# SCH_GW.net
KiCad netlist of a schematic drawn in Altium Designer
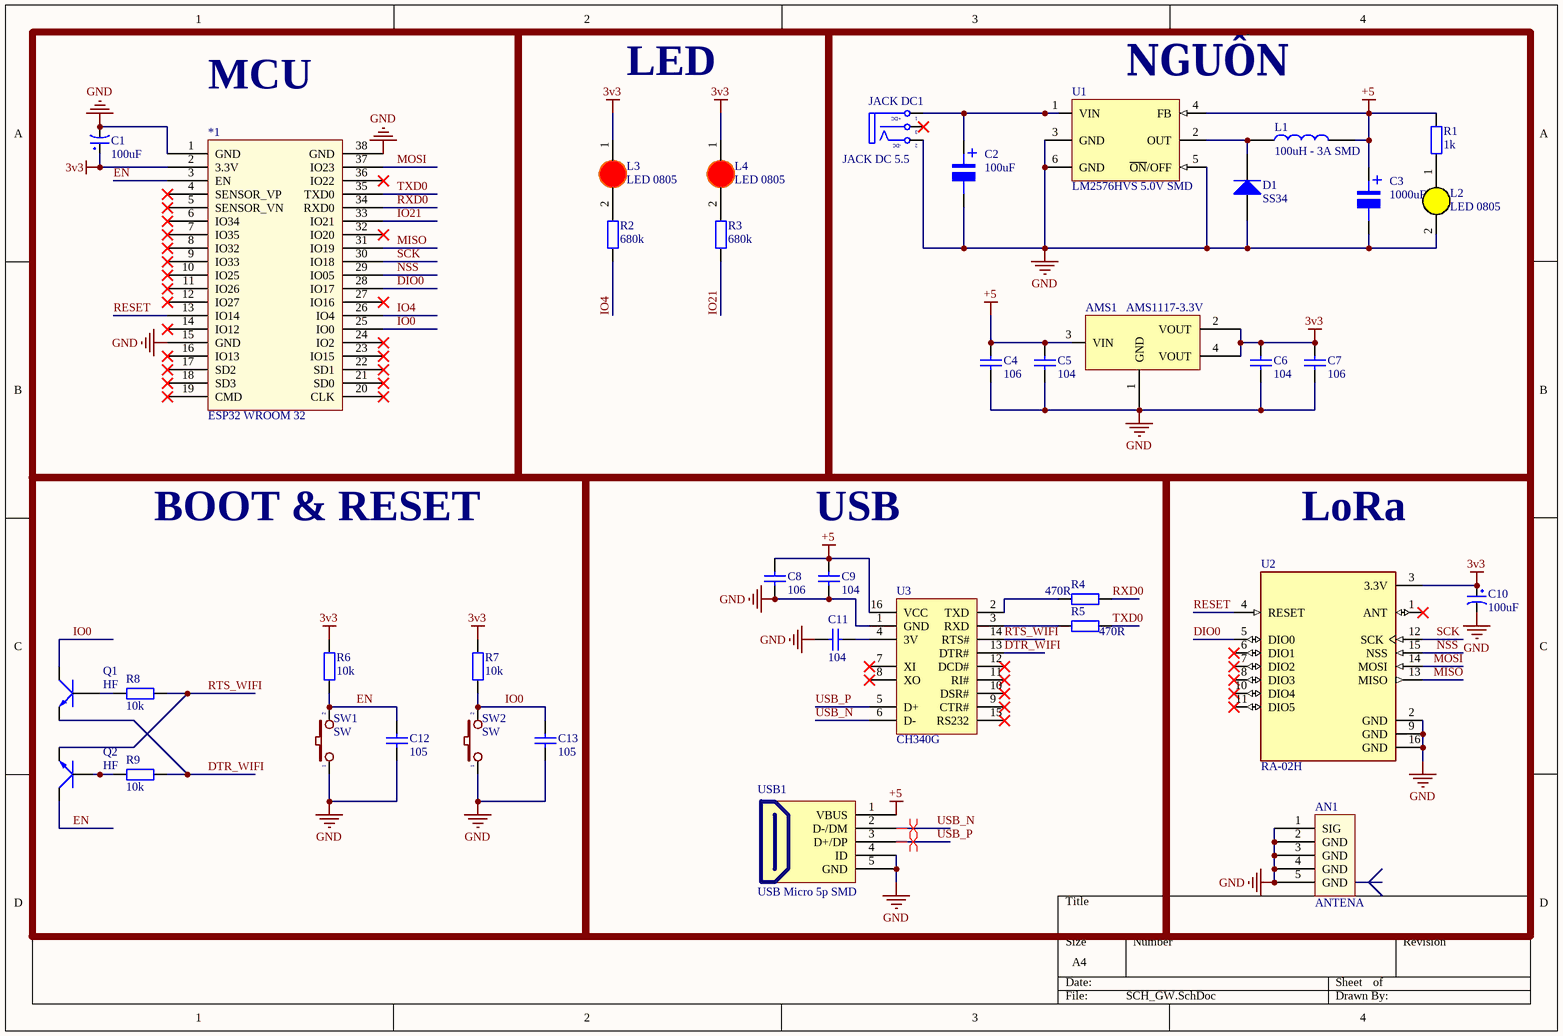
[diagram p0: SCH_GW.SchDoc]

(export (version "E")
  (design (tool "Eeschema 10.0.6"))
  (components
    (comp (ref "*1")
      (value "ESP32 WROOM 32")
      (footprint "ESP32-WROOM-32D")
      (libsource (lib "Altium_Lib_by_KhueNguyenCreator") (part "ESP32 WROOM 32"))
    )
    (comp (ref "AMS1")
      (value "AMS1117-3.3V")
      (footprint "SOT223")
      (description "Dán")
      (libsource (lib "Altium_Lib_by_KhueNguyenCreator") (part "AMS1117 SMD"))
    )
    (comp (ref "AN1")
      (value "ANTENA")
      (footprint "DE ANTEN SMA CONG")
      (description "Generic Antenna")
      (libsource (lib "Altium_Lib_by_KhueNguyenCreator") (part "ANTEN SMA CONG"))
    )
    (comp (ref "C1")
      (value "100uF")
      (footprint "tu tantalum smd3528")
      (description "Dán")
      (libsource (lib "Altium_Lib_by_KhueNguyenCreator") (part "Tu tantalum 100uF 6.3V SMD3528"))
    )
    (comp (ref "C2")
      (value "100uF")
      (footprint "tu nhom 10 (g)")
      (description "Dán")
      (libsource (lib "Altium_Lib_by_KhueNguyenCreator") (part "Tu Nhom 100uF 35V"))
    )
    (comp (ref "C3")
      (value "1000uF")
      (footprint "tu nhom 10 (G)")
      (description "Dán")
      (libsource (lib "Altium_Lib_by_KhueNguyenCreator") (part "Tu Nhom 1000uF 10V"))
    )
    (comp (ref "C4")
      (value "106")
      (footprint "tu 0805")
      (description "Dán")
      (libsource (lib "Altium_Lib_by_KhueNguyenCreator") (part "Tu 0805 106 16V 10%"))
    )
    (comp (ref "C5")
      (value "104")
      (footprint "tu 0805")
      (description "Dán")
      (libsource (lib "Altium_Lib_by_KhueNguyenCreator") (part "Tu 0805 104 50V 10%"))
    )
    (comp (ref "C6")
      (value "104")
      (footprint "tu 0805")
      (description "Dán")
      (libsource (lib "Altium_Lib_by_KhueNguyenCreator") (part "Tu 0805 104 50V 10%"))
    )
    (comp (ref "C7")
      (value "106")
      (footprint "tu 0805")
      (description "Dán")
      (libsource (lib "Altium_Lib_by_KhueNguyenCreator") (part "Tu 0805 106 16V 10%"))
    )
    (comp (ref "C8")
      (value "106")
      (footprint "tu 0805")
      (description "Dán")
      (libsource (lib "Altium_Lib_by_KhueNguyenCreator") (part "Tu 0805 106 16V 10%"))
    )
    (comp (ref "C9")
      (value "104")
      (footprint "tu 0805")
      (description "Dán")
      (libsource (lib "Altium_Lib_by_KhueNguyenCreator") (part "Tu 0805 104 50V 10%"))
    )
    (comp (ref "C10")
      (value "100uF")
      (footprint "tu tantalum smd3528")
      (description "Dán")
      (libsource (lib "Altium_Lib_by_KhueNguyenCreator") (part "Tu tantalum 100uF 6.3V SMD3528"))
    )
    (comp (ref "C11")
      (value "104")
      (footprint "tu 0805")
      (description "Dán")
      (libsource (lib "Altium_Lib_by_KhueNguyenCreator") (part "Tu 0805 104 50V 10%"))
    )
    (comp (ref "C12")
      (value "105")
      (footprint "tu 0805")
      (description "Dán")
      (libsource (lib "Altium_Lib_by_KhueNguyenCreator") (part "Tu 0805 105 50V 10%"))
    )
    (comp (ref "C13")
      (value "105")
      (footprint "tu 0805")
      (description "Dán")
      (libsource (lib "Altium_Lib_by_KhueNguyenCreator") (part "Tu 0805 105 50V 10%"))
    )
    (comp (ref "D1")
      (value "SS34")
      (footprint "DIODE SMA")
      (description "Dán")
      (libsource (lib "Altium_Lib_by_KhueNguyenCreator") (part "Diode SS34 ( 1N5822 )"))
    )
    (comp (ref "JACK DC1")
      (value "JACK DC 5.5")
      (footprint "JACK DC 5.5")
      (libsource (lib "Altium_Lib_by_KhueNguyenCreator") (part "JACK DC 5.5"))
    )
    (comp (ref "L1")
      (value "100uH - 3A SMD")
      (footprint "Cuon Cam 12x12x10")
      (description "Dán")
      (libsource (lib "Altium_Lib_by_KhueNguyenCreator") (part "CUON CAM 100uH SMD"))
    )
    (comp (ref "L2")
      (value "LED 0805")
      (footprint "LED-0805-Yellow")
      (description "Dán")
      (libsource (lib "Altium_Lib_by_KhueNguyenCreator") (part "LED 0805 Vang"))
    )
    (comp (ref "L3")
      (value "LED 0805")
      (footprint "LED-0805-Red")
      (description "Dán")
      (libsource (lib "Altium_Lib_by_KhueNguyenCreator") (part "LED 0805 Do"))
    )
    (comp (ref "L4")
      (value "LED 0805")
      (footprint "LED-0805-Red")
      (description "Dán")
      (libsource (lib "Altium_Lib_by_KhueNguyenCreator") (part "LED 0805 Do"))
    )
    (comp (ref "Q1")
      (value "HF")
      (footprint "SOT23")
      (description "NPN transistor")
      (libsource (lib "Altium_Lib_by_KhueNguyenCreator") (part "C1815 HF SMD"))
    )
    (comp (ref "Q2")
      (value "HF")
      (footprint "SOT23")
      (description "NPN transistor")
      (libsource (lib "Altium_Lib_by_KhueNguyenCreator") (part "C1815 HF SMD"))
    )
    (comp (ref "R1")
      (value "1k")
      (footprint "tro smd 0805")
      (description "Dán")
      (libsource (lib "Altium_Lib_by_KhueNguyenCreator") (part "Tro 0805 1% 1k"))
    )
    (comp (ref "R2")
      (value "680k")
      (footprint "Tro SMD 0805")
      (description "Dán")
      (libsource (lib "Altium_Lib_by_KhueNguyenCreator") (part "Tro 0805 5% 680k"))
    )
    (comp (ref "R3")
      (value "680k")
      (footprint "Tro SMD 0805")
      (description "Dán")
      (libsource (lib "Altium_Lib_by_KhueNguyenCreator") (part "Tro 0805 5% 680k"))
    )
    (comp (ref "R4")
      (value "470R")
      (footprint "Tro SMD 0805")
      (description "Dán")
      (libsource (lib "Altium_Lib_by_KhueNguyenCreator") (part "Tro 0805 5% 470R"))
    )
    (comp (ref "R5")
      (value "470R")
      (footprint "Tro SMD 0805")
      (description "Dán")
      (libsource (lib "Altium_Lib_by_KhueNguyenCreator") (part "Tro 0805 5% 470R"))
    )
    (comp (ref "R6")
      (value "10k")
      (footprint "tro smd 0805")
      (description "Dán")
      (libsource (lib "Altium_Lib_by_KhueNguyenCreator") (part "Tro 0805 1% 10k"))
    )
    (comp (ref "R7")
      (value "10k")
      (footprint "tro smd 0805")
      (description "Dán")
      (libsource (lib "Altium_Lib_by_KhueNguyenCreator") (part "Tro 0805 1% 10k"))
    )
    (comp (ref "R8")
      (value "10k")
      (footprint "tro smd 0805")
      (description "Dán")
      (libsource (lib "Altium_Lib_by_KhueNguyenCreator") (part "Tro 0805 1% 10k"))
    )
    (comp (ref "R9")
      (value "10k")
      (footprint "tro smd 0805")
      (description "Dán")
      (libsource (lib "Altium_Lib_by_KhueNguyenCreator") (part "Tro 0805 1% 10k"))
    )
    (comp (ref "SW1")
      (value "SW")
      (footprint "SW1-DIP")
      (description "Switch button 2 pin")
      (libsource (lib "TechMT.VN_Lib_Project v2") (part "SW2"))
    )
    (comp (ref "SW2")
      (value "SW")
      (footprint "SW1-DIP")
      (description "Switch button 2 pin")
      (libsource (lib "TechMT.VN_Lib_Project v2") (part "SW2"))
    )
    (comp (ref "U1")
      (value "LM2576HVS 5.0V SMD")
      (footprint "TO263-5")
      (description "Dán")
      (libsource (lib "Altium_Lib_by_KhueNguyenCreator") (part "LM2576HVS 5.0V SMD"))
    )
    (comp (ref "U2")
      (value "RA-02H")
      (footprint "XCVR_RA-01H")
      (description "Ai-Thinker Lora Series Module")
      (fields (field (name "MF") "AI-Thinker") (field (name "MP") "RA-01H"))
      (libsource (lib "mySche") (part "RA-02H"))
    )
    (comp (ref "U3")
      (value "CH340G")
      (footprint "SO16")
      (description "High and Low Side Driver")
      (fields (field (name "PUBLISHER") "Altium Limited"))
      (libsource (lib "TechMT.VN_Lib_Project v2") (part "CH340G"))
    )
    (comp (ref "USB1")
      (value "USB Micro 5p SMD")
      (footprint "USB Micro 5p SMD")
      (description "USB Type B")
      (libsource (lib "Altium_Lib_by_KhueNguyenCreator") (part "USB Micro 5p SMD"))
    )
  )
  (nets
    (net (code "1") (name "+5") (class "Default")
      (node (ref "AMS1") (pin "3") (pinfunction "VIN_3") (pintype "passive"))
      (node (ref "C3") (pin "1") (pinfunction "1_1") (pintype "passive"))
      (node (ref "C4") (pin "1") (pinfunction "1_1") (pintype "passive"))
      (node (ref "C5") (pin "1") (pinfunction "1_1") (pintype "passive"))
      (node (ref "C8") (pin "1") (pinfunction "1_1") (pintype "passive"))
      (node (ref "C9") (pin "1") (pinfunction "1_1") (pintype "passive"))
      (node (ref "L1") (pin "2") (pinfunction "2_2") (pintype "passive"))
      (node (ref "R1") (pin "2") (pinfunction "2_2") (pintype "passive"))
      (node (ref "U1") (pin "4") (pinfunction "FB_4") (pintype "input"))
      (node (ref "U3") (pin "16") (pinfunction "VCC_16") (pintype "passive"))
      (node (ref "USB1") (pin "1") (pinfunction "VBUS_1") (pintype "passive"))
    )
    (net (code "2") (name "/DIO0") (class "Default")
      (node (ref "*1") (pin "28") (pinfunction "IO17_28") (pintype "passive"))
      (node (ref "U2") (pin "5") (pinfunction "DIO0_5") (pintype "bidirectional"))
    )
    (net (code "3") (name "/DTR_WIFI") (class "Default")
      (node (ref "Q1") (pin "2") (pinfunction "E_2") (pintype "passive"))
      (node (ref "R9") (pin "2") (pinfunction "2_2") (pintype "passive"))
      (node (ref "U3") (pin "13") (pinfunction "DTR#_13") (pintype "passive"))
    )
    (net (code "4") (name "/EN") (class "Default")
      (node (ref "*1") (pin "3") (pinfunction "EN_3") (pintype "passive"))
      (node (ref "C12") (pin "1") (pinfunction "1_1") (pintype "passive"))
      (node (ref "Q2") (pin "3") (pinfunction "C_3") (pintype "passive"))
      (node (ref "R6") (pin "1") (pinfunction "1_1") (pintype "passive"))
      (node (ref "SW1") (pin "2") (pinfunction "2_2") (pintype "passive"))
    )
    (net (code "5") (name "/IO0") (class "Default")
      (node (ref "*1") (pin "25") (pinfunction "IO0_25") (pintype "passive"))
      (node (ref "C13") (pin "1") (pinfunction "1_1") (pintype "passive"))
      (node (ref "Q1") (pin "3") (pinfunction "C_3") (pintype "passive"))
      (node (ref "R7") (pin "1") (pinfunction "1_1") (pintype "passive"))
      (node (ref "SW2") (pin "2") (pinfunction "2_2") (pintype "passive"))
    )
    (net (code "6") (name "/IO4") (class "Default")
      (node (ref "*1") (pin "26") (pinfunction "IO4_26") (pintype "passive"))
      (node (ref "R2") (pin "1") (pinfunction "1_1") (pintype "passive"))
    )
    (net (code "7") (name "/IO21") (class "Default")
      (node (ref "*1") (pin "33") (pinfunction "IO21_33") (pintype "passive"))
      (node (ref "R3") (pin "1") (pinfunction "1_1") (pintype "passive"))
    )
    (net (code "8") (name "/MISO") (class "Default")
      (node (ref "*1") (pin "31") (pinfunction "IO19_31") (pintype "passive"))
      (node (ref "U2") (pin "13") (pinfunction "MISO_13") (pintype "output"))
    )
    (net (code "9") (name "/MOSI") (class "Default")
      (node (ref "*1") (pin "37") (pinfunction "IO23_37") (pintype "passive"))
      (node (ref "U2") (pin "14") (pinfunction "MOSI_14") (pintype "input"))
    )
    (net (code "10") (name "/NSS") (class "Default")
      (node (ref "*1") (pin "29") (pinfunction "IO05_29") (pintype "passive"))
      (node (ref "U2") (pin "15") (pinfunction "NSS_15") (pintype "input"))
    )
    (net (code "11") (name "/RESET") (class "Default")
      (node (ref "*1") (pin "13") (pinfunction "IO14_13") (pintype "passive"))
      (node (ref "U2") (pin "4") (pinfunction "RESET_4") (pintype "input"))
    )
    (net (code "12") (name "/RTS_WIFI") (class "Default")
      (node (ref "Q2") (pin "2") (pinfunction "E_2") (pintype "passive"))
      (node (ref "R8") (pin "2") (pinfunction "2_2") (pintype "passive"))
      (node (ref "U3") (pin "14") (pinfunction "RTS#_14") (pintype "passive"))
    )
    (net (code "13") (name "/RXD0") (class "Default")
      (node (ref "*1") (pin "34") (pinfunction "RXD0_34") (pintype "passive"))
      (node (ref "R4") (pin "2") (pinfunction "2_2") (pintype "passive"))
    )
    (net (code "14") (name "/SCK") (class "Default")
      (node (ref "*1") (pin "30") (pinfunction "IO18_30") (pintype "passive"))
      (node (ref "U2") (pin "12") (pinfunction "SCK_12") (pintype "input"))
    )
    (net (code "15") (name "/TXD0") (class "Default")
      (node (ref "*1") (pin "35") (pinfunction "TXD0_35") (pintype "passive"))
      (node (ref "R5") (pin "2") (pinfunction "2_2") (pintype "passive"))
    )
    (net (code "16") (name "/USB_N") (class "Default")
      (node (ref "U3") (pin "6") (pinfunction "D-_6") (pintype "passive"))
      (node (ref "USB1") (pin "2") (pinfunction "D-/DM_2") (pintype "passive"))
    )
    (net (code "17") (name "/USB_P") (class "Default")
      (node (ref "U3") (pin "5") (pinfunction "D+_5") (pintype "passive"))
      (node (ref "USB1") (pin "3") (pinfunction "D+/DP_3") (pintype "passive"))
    )
    (net (code "18") (name "3v3") (class "Default")
      (node (ref "*1") (pin "2") (pinfunction "3.3V_2") (pintype "passive"))
      (node (ref "AMS1") (pin "2") (pinfunction "VOUT_2") (pintype "passive"))
      (node (ref "AMS1") (pin "4") (pinfunction "VOUT_4") (pintype "passive"))
      (node (ref "C1") (pin "1") (pinfunction "1_1") (pintype "passive"))
      (node (ref "C10") (pin "1") (pinfunction "1_1") (pintype "passive"))
      (node (ref "C6") (pin "1") (pinfunction "1_1") (pintype "passive"))
      (node (ref "C7") (pin "1") (pinfunction "1_1") (pintype "passive"))
      (node (ref "L3") (pin "1") (pinfunction "A_1") (pintype "passive"))
      (node (ref "L4") (pin "1") (pinfunction "A_1") (pintype "passive"))
      (node (ref "R6") (pin "2") (pinfunction "2_2") (pintype "passive"))
      (node (ref "R7") (pin "2") (pinfunction "2_2") (pintype "passive"))
      (node (ref "U2") (pin "3") (pinfunction "3.3V_3") (pintype "power_in"))
    )
    (net (code "19") (name "GND") (class "Default")
      (node (ref "*1") (pin "1") (pinfunction "GND_1") (pintype "passive"))
      (node (ref "*1") (pin "15") (pinfunction "GND_15") (pintype "passive"))
      (node (ref "*1") (pin "38") (pinfunction "GND_38") (pintype "passive"))
      (node (ref "AMS1") (pin "1") (pinfunction "GND_1") (pintype "passive"))
      (node (ref "AN1") (pin "1") (pinfunction "SIG_1") (pintype "passive"))
      (node (ref "AN1") (pin "2") (pinfunction "GND_2") (pintype "passive"))
      (node (ref "AN1") (pin "3") (pinfunction "GND_3") (pintype "passive"))
      (node (ref "AN1") (pin "4") (pinfunction "GND_4") (pintype "passive"))
      (node (ref "AN1") (pin "5") (pinfunction "GND_5") (pintype "passive"))
      (node (ref "C1") (pin "2") (pinfunction "2_2") (pintype "passive"))
      (node (ref "C10") (pin "2") (pinfunction "2_2") (pintype "passive"))
      (node (ref "C11") (pin "2") (pinfunction "2_2") (pintype "passive"))
      (node (ref "C12") (pin "2") (pinfunction "2_2") (pintype "passive"))
      (node (ref "C13") (pin "2") (pinfunction "2_2") (pintype "passive"))
      (node (ref "C2") (pin "2") (pinfunction "2_2") (pintype "passive"))
      (node (ref "C3") (pin "2") (pinfunction "2_2") (pintype "passive"))
      (node (ref "C4") (pin "2") (pinfunction "2_2") (pintype "passive"))
      (node (ref "C5") (pin "2") (pinfunction "2_2") (pintype "passive"))
      (node (ref "C6") (pin "2") (pinfunction "2_2") (pintype "passive"))
      (node (ref "C7") (pin "2") (pinfunction "2_2") (pintype "passive"))
      (node (ref "C8") (pin "2") (pinfunction "2_2") (pintype "passive"))
      (node (ref "C9") (pin "2") (pinfunction "2_2") (pintype "passive"))
      (node (ref "D1") (pin "1") (pinfunction "A_1") (pintype "passive"))
      (node (ref "JACK DC1") (pin "2") (pinfunction "TN_2") (pintype "passive"))
      (node (ref "L2") (pin "2") (pinfunction "K_2") (pintype "passive"))
      (node (ref "SW1") (pin "1") (pinfunction "1_1") (pintype "passive"))
      (node (ref "SW2") (pin "1") (pinfunction "1_1") (pintype "passive"))
      (node (ref "U1") (pin "3") (pinfunction "GND_3") (pintype "power_in"))
      (node (ref "U1") (pin "5") (pinfunction "~{ON}/OFF_5") (pintype "input"))
      (node (ref "U1") (pin "6") (pinfunction "GND_6") (pintype "passive"))
      (node (ref "U2") (pin "16") (pinfunction "GND_16") (pintype "power_in"))
      (node (ref "U2") (pin "2") (pinfunction "GND_2") (pintype "power_in"))
      (node (ref "U2") (pin "9") (pinfunction "GND_9") (pintype "power_in"))
      (node (ref "U3") (pin "1") (pinfunction "GND_1") (pintype "passive"))
      (node (ref "USB1") (pin "4") (pinfunction "ID_4") (pintype "passive"))
      (node (ref "USB1") (pin "5") (pinfunction "GND_5") (pintype "passive"))
    )
    (net (code "20") (name "Net-(D1-K)") (class "Default")
      (node (ref "D1") (pin "2") (pinfunction "K_2") (pintype "passive"))
      (node (ref "L1") (pin "1") (pinfunction "1_1") (pintype "passive"))
      (node (ref "U1") (pin "2") (pinfunction "OUT_2") (pintype "power_in"))
    )
    (net (code "21") (name "Net-(JACK DC1-T)") (class "Default")
      (node (ref "C2") (pin "1") (pinfunction "1_1") (pintype "passive"))
      (node (ref "JACK DC1") (pin "1") (pinfunction "T_1") (pintype "passive"))
      (node (ref "U1") (pin "1") (pinfunction "VIN_1") (pintype "power_in"))
    )
    (net (code "22") (name "Net-(L2-A)") (class "Default")
      (node (ref "L2") (pin "1") (pinfunction "A_1") (pintype "passive"))
      (node (ref "R1") (pin "1") (pinfunction "1_1") (pintype "passive"))
    )
    (net (code "23") (name "Net-(L3-K)") (class "Default")
      (node (ref "L3") (pin "2") (pinfunction "K_2") (pintype "passive"))
      (node (ref "R2") (pin "2") (pinfunction "2_2") (pintype "passive"))
    )
    (net (code "24") (name "Net-(L4-K)") (class "Default")
      (node (ref "L4") (pin "2") (pinfunction "K_2") (pintype "passive"))
      (node (ref "R3") (pin "2") (pinfunction "2_2") (pintype "passive"))
    )
    (net (code "25") (name "Net-(Q1-B)") (class "Default")
      (node (ref "Q1") (pin "1") (pinfunction "B_1") (pintype "passive"))
      (node (ref "R8") (pin "1") (pinfunction "1_1") (pintype "passive"))
    )
    (net (code "26") (name "Net-(Q2-B)") (class "Default")
      (node (ref "Q2") (pin "1") (pinfunction "B_1") (pintype "passive"))
      (node (ref "R9") (pin "1") (pinfunction "1_1") (pintype "passive"))
    )
    (net (code "27") (name "Net-(U3-3V)") (class "Default")
      (node (ref "C11") (pin "1") (pinfunction "1_1") (pintype "passive"))
      (node (ref "U3") (pin "4") (pinfunction "3V_4") (pintype "passive"))
    )
    (net (code "28") (name "Net-(U3-RXD)") (class "Default")
      (node (ref "R5") (pin "1") (pinfunction "1_1") (pintype "passive"))
      (node (ref "U3") (pin "3") (pinfunction "RXD_3") (pintype "passive"))
    )
    (net (code "29") (name "Net-(U3-TXD)") (class "Default")
      (node (ref "R4") (pin "1") (pinfunction "1_1") (pintype "passive"))
      (node (ref "U3") (pin "2") (pinfunction "TXD_2") (pintype "passive"))
    )
    (net (code "30") (name "unconnected-(*1-CLK-Pad20)") (class "Default")
      (node (ref "*1") (pin "20") (pinfunction "CLK_20") (pintype "passive+no_connect"))
    )
    (net (code "31") (name "unconnected-(*1-CMD-Pad19)") (class "Default")
      (node (ref "*1") (pin "19") (pinfunction "CMD_19") (pintype "passive+no_connect"))
    )
    (net (code "32") (name "unconnected-(*1-IO2-Pad24)") (class "Default")
      (node (ref "*1") (pin "24") (pinfunction "IO2_24") (pintype "passive+no_connect"))
    )
    (net (code "33") (name "unconnected-(*1-IO12-Pad14)") (class "Default")
      (node (ref "*1") (pin "14") (pinfunction "IO12_14") (pintype "passive+no_connect"))
    )
    (net (code "34") (name "unconnected-(*1-IO13-Pad16)") (class "Default")
      (node (ref "*1") (pin "16") (pinfunction "IO13_16") (pintype "passive+no_connect"))
    )
    (net (code "35") (name "unconnected-(*1-IO15-Pad23)") (class "Default")
      (node (ref "*1") (pin "23") (pinfunction "IO15_23") (pintype "passive+no_connect"))
    )
    (net (code "36") (name "unconnected-(*1-IO16-Pad27)") (class "Default")
      (node (ref "*1") (pin "27") (pinfunction "IO16_27") (pintype "passive+no_connect"))
    )
    (net (code "37") (name "unconnected-(*1-IO20-Pad32)") (class "Default")
      (node (ref "*1") (pin "32") (pinfunction "IO20_32") (pintype "passive+no_connect"))
    )
    (net (code "38") (name "unconnected-(*1-IO22-Pad36)") (class "Default")
      (node (ref "*1") (pin "36") (pinfunction "IO22_36") (pintype "passive+no_connect"))
    )
    (net (code "39") (name "unconnected-(*1-IO25-Pad10)") (class "Default")
      (node (ref "*1") (pin "10") (pinfunction "IO25_10") (pintype "passive+no_connect"))
    )
    (net (code "40") (name "unconnected-(*1-IO26-Pad11)") (class "Default")
      (node (ref "*1") (pin "11") (pinfunction "IO26_11") (pintype "passive+no_connect"))
    )
    (net (code "41") (name "unconnected-(*1-IO27-Pad12)") (class "Default")
      (node (ref "*1") (pin "12") (pinfunction "IO27_12") (pintype "passive+no_connect"))
    )
    (net (code "42") (name "unconnected-(*1-IO32-Pad8)") (class "Default")
      (node (ref "*1") (pin "8") (pinfunction "IO32_8") (pintype "passive+no_connect"))
    )
    (net (code "43") (name "unconnected-(*1-IO33-Pad9)") (class "Default")
      (node (ref "*1") (pin "9") (pinfunction "IO33_9") (pintype "passive+no_connect"))
    )
    (net (code "44") (name "unconnected-(*1-IO34-Pad6)") (class "Default")
      (node (ref "*1") (pin "6") (pinfunction "IO34_6") (pintype "passive+no_connect"))
    )
    (net (code "45") (name "unconnected-(*1-IO35-Pad7)") (class "Default")
      (node (ref "*1") (pin "7") (pinfunction "IO35_7") (pintype "passive+no_connect"))
    )
    (net (code "46") (name "unconnected-(*1-SD0-Pad21)") (class "Default")
      (node (ref "*1") (pin "21") (pinfunction "SD0_21") (pintype "passive+no_connect"))
    )
    (net (code "47") (name "unconnected-(*1-SD1-Pad22)") (class "Default")
      (node (ref "*1") (pin "22") (pinfunction "SD1_22") (pintype "passive+no_connect"))
    )
    (net (code "48") (name "unconnected-(*1-SD2-Pad17)") (class "Default")
      (node (ref "*1") (pin "17") (pinfunction "SD2_17") (pintype "passive+no_connect"))
    )
    (net (code "49") (name "unconnected-(*1-SD3-Pad18)") (class "Default")
      (node (ref "*1") (pin "18") (pinfunction "SD3_18") (pintype "passive+no_connect"))
    )
    (net (code "50") (name "unconnected-(*1-SENSOR_VN-Pad5)") (class "Default")
      (node (ref "*1") (pin "5") (pinfunction "SENSOR_VN_5") (pintype "passive+no_connect"))
    )
    (net (code "51") (name "unconnected-(*1-SENSOR_VP-Pad4)") (class "Default")
      (node (ref "*1") (pin "4") (pinfunction "SENSOR_VP_4") (pintype "passive+no_connect"))
    )
    (net (code "52") (name "unconnected-(JACK DC1-S-Pad3)") (class "Default")
      (node (ref "JACK DC1") (pin "3") (pinfunction "S_3") (pintype "power_in+no_connect"))
    )
    (net (code "53") (name "unconnected-(U2-ANT-Pad1)") (class "Default")
      (node (ref "U2") (pin "1") (pinfunction "ANT_1") (pintype "bidirectional+no_connect"))
    )
    (net (code "54") (name "unconnected-(U2-DIO1-Pad6)") (class "Default")
      (node (ref "U2") (pin "6") (pinfunction "DIO1_6") (pintype "bidirectional+no_connect"))
    )
    (net (code "55") (name "unconnected-(U2-DIO2-Pad7)") (class "Default")
      (node (ref "U2") (pin "7") (pinfunction "DIO2_7") (pintype "bidirectional+no_connect"))
    )
    (net (code "56") (name "unconnected-(U2-DIO3-Pad8)") (class "Default")
      (node (ref "U2") (pin "8") (pinfunction "DIO3_8") (pintype "bidirectional+no_connect"))
    )
    (net (code "57") (name "unconnected-(U2-DIO4-Pad10)") (class "Default")
      (node (ref "U2") (pin "10") (pinfunction "DIO4_10") (pintype "bidirectional+no_connect"))
    )
    (net (code "58") (name "unconnected-(U2-DIO5-Pad11)") (class "Default")
      (node (ref "U2") (pin "11") (pinfunction "DIO5_11") (pintype "bidirectional+no_connect"))
    )
    (net (code "59") (name "unconnected-(U3-CTR#-Pad9)") (class "Default")
      (node (ref "U3") (pin "9") (pinfunction "CTR#_9") (pintype "passive+no_connect"))
    )
    (net (code "60") (name "unconnected-(U3-DCD#-Pad12)") (class "Default")
      (node (ref "U3") (pin "12") (pinfunction "DCD#_12") (pintype "passive+no_connect"))
    )
    (net (code "61") (name "unconnected-(U3-DSR#-Pad10)") (class "Default")
      (node (ref "U3") (pin "10") (pinfunction "DSR#_10") (pintype "passive+no_connect"))
    )
    (net (code "62") (name "unconnected-(U3-RI#-Pad11)") (class "Default")
      (node (ref "U3") (pin "11") (pinfunction "RI#_11") (pintype "passive+no_connect"))
    )
    (net (code "63") (name "unconnected-(U3-RS232-Pad15)") (class "Default")
      (node (ref "U3") (pin "15") (pinfunction "RS232_15") (pintype "passive+no_connect"))
    )
    (net (code "64") (name "unconnected-(U3-XI-Pad7)") (class "Default")
      (node (ref "U3") (pin "7") (pinfunction "XI_7") (pintype "passive+no_connect"))
    )
    (net (code "65") (name "unconnected-(U3-XO-Pad8)") (class "Default")
      (node (ref "U3") (pin "8") (pinfunction "XO_8") (pintype "passive+no_connect"))
    )
  )
)
